# Loop_Schematic_r1_1_easyeda.net
KiCad netlist of a schematic drawn in EasyEDA
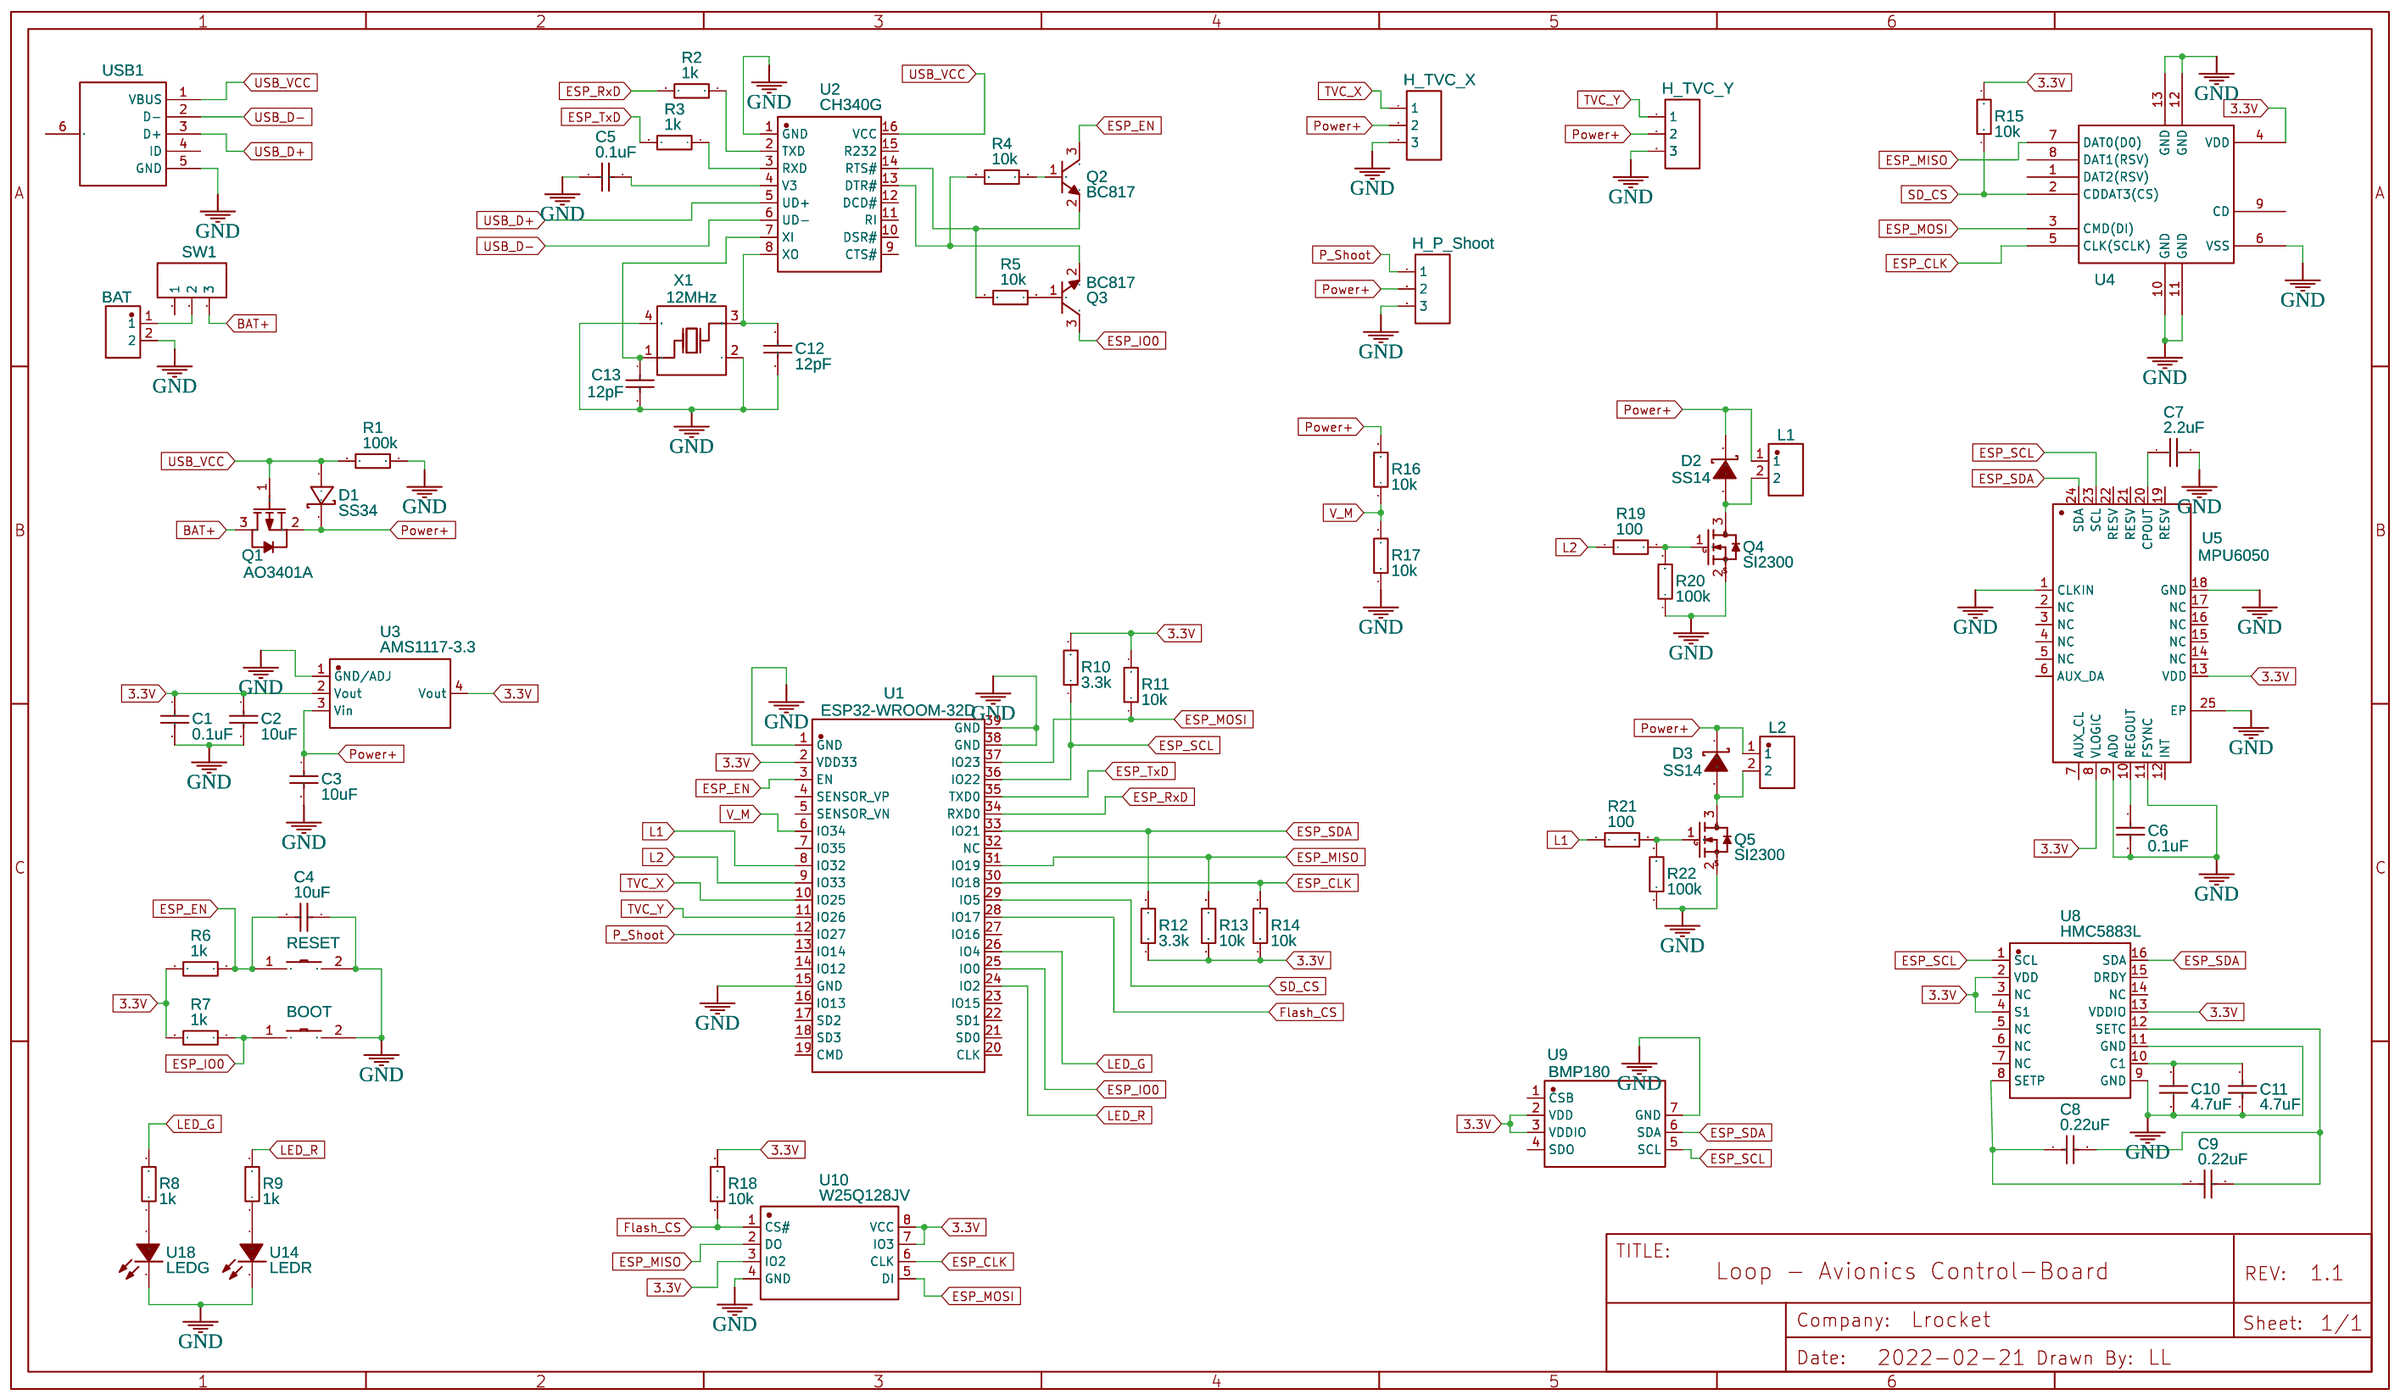
[diagram p0: schematic sheet]

(export (version "E")
  (design (tool "Eeschema 10.0.6"))
  (components
    (comp (ref "BAT")
      (value "XY308-2.54-2P")
      (fields (field (name "BOM_Supplier Part") "C557685"))
      (libsource (lib "") (part "XY308-2.54-2P"))
    )
    (comp (ref "BOOT")
      (value "TS-1101-C-W")
      (fields (field (name "BOM_Supplier Part") "C318938"))
      (libsource (lib "") (part "TS-1101-C-W_1"))
    )
    (comp (ref "C1")
      (value "0.1uF")
      (fields
        (field (name "BOM_Manufacturer Part") "CC0603KRX7R9BB103")
        (field (name "BOM_Supplier Part") "C100042")
      )
      (libsource (lib "") (part "CC0603KRX7R9BB103"))
    )
    (comp (ref "C2")
      (value "10uF")
      (fields
        (field (name "BOM_Manufacturer Part") "CC0603KRX7R9BB103")
        (field (name "BOM_Supplier Part") "C100042")
      )
      (libsource (lib "") (part "CC0603KRX7R9BB103"))
    )
    (comp (ref "C3")
      (value "10uF")
      (fields
        (field (name "BOM_Manufacturer Part") "CC0603KRX7R9BB103")
        (field (name "BOM_Supplier Part") "C100042")
      )
      (libsource (lib "") (part "CC0603KRX7R9BB103"))
    )
    (comp (ref "C4")
      (value "10uF")
      (fields
        (field (name "BOM_Manufacturer Part") "CC0603KRX7R9BB103")
        (field (name "BOM_Supplier Part") "C100042")
      )
      (libsource (lib "") (part "CC0603KRX7R9BB103_3"))
    )
    (comp (ref "C5")
      (value "0.1uF")
      (fields
        (field (name "BOM_Manufacturer Part") "CC0603KRX7R9BB103")
        (field (name "BOM_Supplier Part") "C100042")
      )
      (libsource (lib "") (part "CC0603KRX7R9BB103_3"))
    )
    (comp (ref "C6")
      (value "0.1uF")
      (fields
        (field (name "BOM_Manufacturer Part") "CC0603KRX7R9BB103")
        (field (name "BOM_Supplier Part") "C100042")
      )
      (libsource (lib "") (part "CC0603KRX7R9BB103_2"))
    )
    (comp (ref "C7")
      (value "2.2uF")
      (fields
        (field (name "BOM_Manufacturer Part") "CC0603KRX7R9BB103")
        (field (name "BOM_Supplier Part") "C100042")
      )
      (libsource (lib "") (part "CC0603KRX7R9BB103_1"))
    )
    (comp (ref "C8")
      (value "0.22uF")
      (fields
        (field (name "BOM_Manufacturer Part") "CC0603KRX7R9BB103")
        (field (name "BOM_Supplier Part") "C100042")
      )
      (libsource (lib "") (part "CC0603KRX7R9BB103_1"))
    )
    (comp (ref "C9")
      (value "0.22uF")
      (fields
        (field (name "BOM_Manufacturer Part") "DLC1.5P-C0805")
        (field (name "BOM_Supplier Part") "C9900002366")
      )
      (libsource (lib "") (part "DLC1.5P-C0805"))
    )
    (comp (ref "C10")
      (value "4.7uF")
      (fields
        (field (name "BOM_Manufacturer Part") "CC0603KRX7R9BB103")
        (field (name "BOM_Supplier Part") "C100042")
      )
      (libsource (lib "") (part "CC0603KRX7R9BB103"))
    )
    (comp (ref "C11")
      (value "4.7uF")
      (fields
        (field (name "BOM_Manufacturer Part") "DLC1.5P-C0805")
        (field (name "BOM_Supplier Part") "C9900002366")
      )
      (libsource (lib "") (part "DLC1.5P-C0805_1"))
    )
    (comp (ref "C12")
      (value "12pF")
      (fields
        (field (name "BOM_Manufacturer Part") "CC0603KRX7R9BB103")
        (field (name "BOM_Supplier Part") "C100042")
      )
      (libsource (lib "") (part "CC0603KRX7R9BB103"))
    )
    (comp (ref "C13")
      (value "12pF")
      (fields
        (field (name "BOM_Manufacturer Part") "CC0603KRX7R9BB103")
        (field (name "BOM_Supplier Part") "C100042")
      )
      (libsource (lib "") (part "CC0603KRX7R9BB103"))
    )
    (comp (ref "D1")
      (value "SS34")
      (fields (field (name "BOM_Supplier Part") "C8678"))
      (libsource (lib "") (part "SS34_C8678"))
    )
    (comp (ref "D2")
      (value "SS14")
      (fields (field (name "BOM_Supplier Part") "C2480"))
      (libsource (lib "") (part "SS14"))
    )
    (comp (ref "D3")
      (value "SS14")
      (fields (field (name "BOM_Supplier Part") "C2480"))
      (libsource (lib "") (part "SS14"))
    )
    (comp (ref "L1")
      (value "XY308-2.54-2P")
      (fields (field (name "BOM_Supplier Part") "C557685"))
      (libsource (lib "") (part "XY308-2.54-2P_1"))
    )
    (comp (ref "L2")
      (value "XY308-2.54-2P")
      (fields (field (name "BOM_Supplier Part") "C557685"))
      (libsource (lib "") (part "XY308-2.54-2P_1"))
    )
    (comp (ref "P_SHOOT")
      (value "H_P_Shoot")
      (fields
        (field (name "BOM_Manufacturer Part") "Header2.54mm 1*3P")
        (field (name "BOM_Supplier Part") "C49257")
      )
      (libsource (lib "") (part "Header-Male-2.54_1x3_2"))
    )
    (comp (ref "Q1")
      (value "AO3401A")
      (fields (field (name "BOM_Supplier Part") "C15127"))
      (libsource (lib "") (part "AO3401A"))
    )
    (comp (ref "Q2")
      (value "BC817")
      (fields (field (name "BOM_Manufacturer Part") "BC817-25") (field (name "BOM_Supplier Part") "C8588"))
      (libsource (lib "") (part "BC817-25"))
    )
    (comp (ref "Q3")
      (value "BC817")
      (fields (field (name "BOM_Manufacturer Part") "BC817-25") (field (name "BOM_Supplier Part") "C8588"))
      (libsource (lib "") (part "BC817-25_1"))
    )
    (comp (ref "Q4")
      (value "SI2300")
      (fields (field (name "BOM_Supplier Part") "C181085"))
      (libsource (lib "") (part "SI2300"))
    )
    (comp (ref "Q5")
      (value "SI2300")
      (fields (field (name "BOM_Supplier Part") "C181085"))
      (libsource (lib "") (part "SI2300"))
    )
    (comp (ref "R1")
      (value "100k")
      (fields
        (field (name "BOM_Manufacturer Part") "TR0603B10KP05250.1W")
        (field (name "BOM_Supplier Part") "C188363")
      )
      (libsource (lib "") (part "TR0603B10KP05250.1W_2"))
    )
    (comp (ref "R2")
      (value "1k")
      (fields
        (field (name "BOM_Manufacturer Part") "TR0603B10KP05250.1W")
        (field (name "BOM_Supplier Part") "C188363")
      )
      (libsource (lib "") (part "TR0603B10KP05250.1W_2"))
    )
    (comp (ref "R3")
      (value "1k")
      (fields
        (field (name "BOM_Manufacturer Part") "TR0603B10KP05250.1W")
        (field (name "BOM_Supplier Part") "C188363")
      )
      (libsource (lib "") (part "TR0603B10KP05250.1W_2"))
    )
    (comp (ref "R4")
      (value "10k")
      (fields
        (field (name "BOM_Manufacturer Part") "TR0603B10KP05250.1W")
        (field (name "BOM_Supplier Part") "C188363")
      )
      (libsource (lib "") (part "TR0603B10KP05250.1W_2"))
    )
    (comp (ref "R5")
      (value "10k")
      (fields
        (field (name "BOM_Manufacturer Part") "TR0603B10KP05250.1W")
        (field (name "BOM_Supplier Part") "C188363")
      )
      (libsource (lib "") (part "TR0603B10KP05250.1W_2"))
    )
    (comp (ref "R6")
      (value "1k")
      (fields
        (field (name "BOM_Manufacturer Part") "TR0603B10KP05250.1W")
        (field (name "BOM_Supplier Part") "C188363")
      )
      (libsource (lib "") (part "TR0603B10KP05250.1W_2"))
    )
    (comp (ref "R7")
      (value "1k")
      (fields
        (field (name "BOM_Manufacturer Part") "TR0603B10KP05250.1W")
        (field (name "BOM_Supplier Part") "C188363")
      )
      (libsource (lib "") (part "TR0603B10KP05250.1W_2"))
    )
    (comp (ref "R8")
      (value "1k")
      (fields
        (field (name "BOM_Manufacturer Part") "TR0603B10KP05250.1W")
        (field (name "BOM_Supplier Part") "C188363")
      )
      (libsource (lib "") (part "TR0603B10KP05250.1W"))
    )
    (comp (ref "R9")
      (value "1k")
      (fields
        (field (name "BOM_Manufacturer Part") "TR0603B10KP05250.1W")
        (field (name "BOM_Supplier Part") "C188363")
      )
      (libsource (lib "") (part "TR0603B10KP05250.1W"))
    )
    (comp (ref "R10")
      (value "3.3k")
      (fields
        (field (name "BOM_Manufacturer Part") "TR0603B10KP05250.1W")
        (field (name "BOM_Supplier Part") "C188363")
      )
      (libsource (lib "") (part "TR0603B10KP05250.1W"))
    )
    (comp (ref "R11")
      (value "10k")
      (fields
        (field (name "BOM_Manufacturer Part") "TR0603B10KP05250.1W")
        (field (name "BOM_Supplier Part") "C188363")
      )
      (libsource (lib "") (part "TR0603B10KP05250.1W"))
    )
    (comp (ref "R12")
      (value "3.3k")
      (fields
        (field (name "BOM_Manufacturer Part") "TR0603B10KP05250.1W")
        (field (name "BOM_Supplier Part") "C188363")
      )
      (libsource (lib "") (part "TR0603B10KP05250.1W"))
    )
    (comp (ref "R13")
      (value "10k")
      (fields
        (field (name "BOM_Manufacturer Part") "TR0603B10KP05250.1W")
        (field (name "BOM_Supplier Part") "C188363")
      )
      (libsource (lib "") (part "TR0603B10KP05250.1W"))
    )
    (comp (ref "R14")
      (value "10k")
      (fields
        (field (name "BOM_Manufacturer Part") "TR0603B10KP05250.1W")
        (field (name "BOM_Supplier Part") "C188363")
      )
      (libsource (lib "") (part "TR0603B10KP05250.1W"))
    )
    (comp (ref "R15")
      (value "10k")
      (fields
        (field (name "BOM_Manufacturer Part") "TR0603B10KP05250.1W")
        (field (name "BOM_Supplier Part") "C188363")
      )
      (libsource (lib "") (part "TR0603B10KP05250.1W"))
    )
    (comp (ref "R16")
      (value "10k")
      (fields
        (field (name "BOM_Manufacturer Part") "TR0603B10KP05250.1W")
        (field (name "BOM_Supplier Part") "C188363")
      )
      (libsource (lib "") (part "TR0603B10KP05250.1W"))
    )
    (comp (ref "R17")
      (value "10k")
      (fields
        (field (name "BOM_Manufacturer Part") "TR0603B10KP05250.1W")
        (field (name "BOM_Supplier Part") "C188363")
      )
      (libsource (lib "") (part "TR0603B10KP05250.1W"))
    )
    (comp (ref "R18")
      (value "10k")
      (fields
        (field (name "BOM_Manufacturer Part") "TR0603B10KP05250.1W")
        (field (name "BOM_Supplier Part") "C188363")
      )
      (libsource (lib "") (part "TR0603B10KP05250.1W"))
    )
    (comp (ref "R19")
      (value "100")
      (fields
        (field (name "BOM_Manufacturer Part") "TR0603B10KP05250.1W")
        (field (name "BOM_Supplier Part") "C188363")
      )
      (libsource (lib "") (part "TR0603B10KP05250.1W_1"))
    )
    (comp (ref "R20")
      (value "100k")
      (fields
        (field (name "BOM_Manufacturer Part") "TR0603B10KP05250.1W")
        (field (name "BOM_Supplier Part") "C188363")
      )
      (libsource (lib "") (part "TR0603B10KP05250.1W"))
    )
    (comp (ref "R21")
      (value "100")
      (fields
        (field (name "BOM_Manufacturer Part") "TR0603B10KP05250.1W")
        (field (name "BOM_Supplier Part") "C188363")
      )
      (libsource (lib "") (part "TR0603B10KP05250.1W_1"))
    )
    (comp (ref "R22")
      (value "100k")
      (fields
        (field (name "BOM_Manufacturer Part") "TR0603B10KP05250.1W")
        (field (name "BOM_Supplier Part") "C188363")
      )
      (libsource (lib "") (part "TR0603B10KP05250.1W"))
    )
    (comp (ref "RESET")
      (value "TS-1101-C-W")
      (fields (field (name "BOM_Supplier Part") "C318938"))
      (libsource (lib "") (part "TS-1101-C-W"))
    )
    (comp (ref "SW1")
      (value "SW1")
      (fields
        (field (name "BOM_Manufacturer Part") "Header2.54mm 1*3P")
        (field (name "BOM_Supplier Part") "C49257")
      )
      (libsource (lib "") (part "Header-Male-2.54_1x3_3"))
    )
    (comp (ref "TVC_X")
      (value "H_TVC_X")
      (fields
        (field (name "BOM_Manufacturer Part") "Header2.54mm 1*3P")
        (field (name "BOM_Supplier Part") "C49257")
      )
      (libsource (lib "") (part "Header-Male-2.54_1x3"))
    )
    (comp (ref "TVC_Y")
      (value "H_TVC_Y")
      (fields
        (field (name "BOM_Manufacturer Part") "Header2.54mm 1*3P")
        (field (name "BOM_Supplier Part") "C49257")
      )
      (libsource (lib "") (part "Header-Male-2.54_1x3_1"))
    )
    (comp (ref "U1")
      (value "ESP32-WROOM-32D")
      (fields (field (name "BOM_Supplier Part") "C473012"))
      (libsource (lib "") (part "ESP32-WROOM-32D"))
    )
    (comp (ref "U2")
      (value "CH340G")
      (fields (field (name "BOM_Supplier Part") "C14267"))
      (libsource (lib "") (part "CH340G"))
    )
    (comp (ref "U3")
      (value "AMS1117-3.3")
      (fields (field (name "BOM_Supplier Part") "C6186"))
      (libsource (lib "") (part "AMS1117-3.3"))
    )
    (comp (ref "U4")
      (value "TF-01A")
      (fields (field (name "BOM_Supplier Part") "C91145"))
      (libsource (lib "") (part "TF-01A"))
    )
    (comp (ref "U5")
      (value "MPU6050")
      (fields
        (field (name "BOM_Manufacturer Part") "MPU6050-YJLTY")
        (field (name "BOM_Supplier Part") "C2912107")
      )
      (libsource (lib "") (part "MPU6050-YJLTY"))
    )
    (comp (ref "U8")
      (value "HMC5883L")
      (fields (field (name "BOM_Supplier Part") "C2859540"))
      (libsource (lib "") (part "HMC5883L"))
    )
    (comp (ref "U9")
      (value "BMP180")
      (fields (field (name "BOM_Supplier Part") "C438474"))
      (libsource (lib "") (part "BMP180"))
    )
    (comp (ref "U10")
      (value "W25Q128JV")
      (fields
        (field (name "BOM_Manufacturer Part") "W25Q128JVSIQTR")
        (field (name "BOM_Supplier Part") "C97521")
      )
      (libsource (lib "") (part "W25Q128JVSIQTR"))
    )
    (comp (ref "U14")
      (value "LEDR")
      (fields (field (name "BOM_Manufacturer Part") "SZYY0603W") (field (name "BOM_Supplier Part") "C434422"))
      (libsource (lib "") (part "SZYY0603W"))
    )
    (comp (ref "U18")
      (value "LEDG")
      (fields (field (name "BOM_Manufacturer Part") "SZYY0603W") (field (name "BOM_Supplier Part") "C434422"))
      (libsource (lib "") (part "SZYY0603W"))
    )
    (comp (ref "USB1")
      (value "USB1")
      (fields
        (field (name "BOM_Manufacturer Part") "U254-051T-4BH83-S1S")
        (field (name "BOM_Supplier Part") "C319160")
      )
      (libsource (lib "") (part "U254-051T-4BH83-S1S"))
    )
    (comp (ref "X1")
      (value "12MHz")
      (fields
        (field (name "BOM_Manufacturer Part") "X322512MOB4SI")
        (field (name "BOM_Supplier Part") "C70565")
      )
      (libsource (lib "") (part "X322512MOB4SI"))
    )
  )
  (nets
    (net (code "1") (name "3.3V") (class "Default")
      (node (ref "C1") (pin "1") (pinfunction "1_1") (pintype "input"))
      (node (ref "C2") (pin "1") (pinfunction "1_1") (pintype "input"))
      (node (ref "R10") (pin "2") (pinfunction "2_2") (pintype "unspecified"))
      (node (ref "R11") (pin "2") (pinfunction "2_2") (pintype "unspecified"))
      (node (ref "R12") (pin "1") (pinfunction "1_1") (pintype "unspecified"))
      (node (ref "R13") (pin "1") (pinfunction "1_1") (pintype "unspecified"))
      (node (ref "R14") (pin "1") (pinfunction "1_1") (pintype "unspecified"))
      (node (ref "R15") (pin "2") (pinfunction "2_2") (pintype "unspecified"))
      (node (ref "R18") (pin "2") (pinfunction "2_2") (pintype "unspecified"))
      (node (ref "R6") (pin "2") (pinfunction "2_2") (pintype "unspecified"))
      (node (ref "R7") (pin "2") (pinfunction "2_2") (pintype "unspecified"))
      (node (ref "U1") (pin "2") (pinfunction "VDD33_2") (pintype "unspecified"))
      (node (ref "U10") (pin "3") (pinfunction "IO2_3") (pintype "unspecified"))
      (node (ref "U10") (pin "7") (pinfunction "IO3_7") (pintype "unspecified"))
      (node (ref "U10") (pin "8") (pinfunction "VCC_8") (pintype "unspecified"))
      (node (ref "U3") (pin "2") (pinfunction "Vout_2") (pintype "unspecified"))
      (node (ref "U3") (pin "4") (pinfunction "Vout_4") (pintype "unspecified"))
      (node (ref "U4") (pin "4") (pinfunction "VDD_4") (pintype "input"))
      (node (ref "U5") (pin "13") (pinfunction "VDD_13") (pintype "unspecified"))
      (node (ref "U5") (pin "8") (pinfunction "VLOGIC_8") (pintype "unspecified"))
      (node (ref "U8") (pin "13") (pinfunction "VDDIO_13") (pintype "unspecified"))
      (node (ref "U8") (pin "2") (pinfunction "VDD_2") (pintype "unspecified"))
      (node (ref "U8") (pin "4") (pinfunction "S1_4") (pintype "unspecified"))
      (node (ref "U9") (pin "2") (pinfunction "VDD_2") (pintype "unspecified"))
      (node (ref "U9") (pin "3") (pinfunction "VDDIO_3") (pintype "unspecified"))
    )
    (net (code "2") (name "BAT+") (class "Default")
      (node (ref "Q1") (pin "3") (pinfunction "D_3") (pintype "unspecified"))
      (node (ref "SW1") (pin "3") (pinfunction "3_3") (pintype "input"))
    )
    (net (code "3") (name "ESP_CLK") (class "Default")
      (node (ref "R14") (pin "2") (pinfunction "2_2") (pintype "unspecified"))
      (node (ref "U1") (pin "30") (pinfunction "IO18_30") (pintype "unspecified"))
      (node (ref "U10") (pin "6") (pinfunction "CLK_6") (pintype "unspecified"))
      (node (ref "U4") (pin "5") (pinfunction "CLK(SCLK)_5") (pintype "input"))
    )
    (net (code "4") (name "ESP_EN") (class "Default")
      (node (ref "C4") (pin "2") (pinfunction "2_2") (pintype "input"))
      (node (ref "Q2") (pin "3") (pinfunction "C_3") (pintype "unspecified"))
      (node (ref "R6") (pin "1") (pinfunction "1_1") (pintype "unspecified"))
      (node (ref "RESET") (pin "1") (pinfunction "1_1") (pintype "unspecified"))
      (node (ref "U1") (pin "3") (pinfunction "EN_3") (pintype "unspecified"))
    )
    (net (code "5") (name "ESP_IO0") (class "Default")
      (node (ref "BOOT") (pin "1") (pinfunction "1_1") (pintype "unspecified"))
      (node (ref "Q3") (pin "3") (pinfunction "C_3") (pintype "unspecified"))
      (node (ref "R7") (pin "1") (pinfunction "1_1") (pintype "unspecified"))
      (node (ref "U1") (pin "25") (pinfunction "IO0_25") (pintype "unspecified"))
    )
    (net (code "6") (name "ESP_MISO") (class "Default")
      (node (ref "R13") (pin "2") (pinfunction "2_2") (pintype "unspecified"))
      (node (ref "U1") (pin "31") (pinfunction "IO19_31") (pintype "unspecified"))
      (node (ref "U10") (pin "2") (pinfunction "DO_2") (pintype "unspecified"))
      (node (ref "U4") (pin "7") (pinfunction "DAT0(D0)_7") (pintype "bidirectional"))
    )
    (net (code "7") (name "ESP_MOSI") (class "Default")
      (node (ref "R11") (pin "1") (pinfunction "1_1") (pintype "unspecified"))
      (node (ref "U1") (pin "37") (pinfunction "IO23_37") (pintype "unspecified"))
      (node (ref "U10") (pin "5") (pinfunction "DI_5") (pintype "unspecified"))
      (node (ref "U4") (pin "3") (pinfunction "CMD(DI)_3") (pintype "input"))
    )
    (net (code "8") (name "ESP_RxD") (class "Default")
      (node (ref "R2") (pin "2") (pinfunction "2_2") (pintype "unspecified"))
      (node (ref "U1") (pin "34") (pinfunction "RXD0_34") (pintype "unspecified"))
    )
    (net (code "9") (name "ESP_SCL") (class "Default")
      (node (ref "R10") (pin "1") (pinfunction "1_1") (pintype "unspecified"))
      (node (ref "U1") (pin "36") (pinfunction "IO22_36") (pintype "unspecified"))
      (node (ref "U5") (pin "23") (pinfunction "SCL_23") (pintype "unspecified"))
      (node (ref "U8") (pin "1") (pinfunction "SCL_1") (pintype "unspecified"))
      (node (ref "U9") (pin "5") (pinfunction "SCL_5") (pintype "unspecified"))
    )
    (net (code "10") (name "ESP_SDA") (class "Default")
      (node (ref "R12") (pin "2") (pinfunction "2_2") (pintype "unspecified"))
      (node (ref "U1") (pin "33") (pinfunction "IO21_33") (pintype "unspecified"))
      (node (ref "U5") (pin "24") (pinfunction "SDA_24") (pintype "unspecified"))
      (node (ref "U8") (pin "16") (pinfunction "SDA_16") (pintype "unspecified"))
      (node (ref "U9") (pin "6") (pinfunction "SDA_6") (pintype "unspecified"))
    )
    (net (code "11") (name "ESP_TxD") (class "Default")
      (node (ref "R3") (pin "2") (pinfunction "2_2") (pintype "unspecified"))
      (node (ref "U1") (pin "35") (pinfunction "TXD0_35") (pintype "unspecified"))
    )
    (net (code "12") (name "Flash_CS") (class "Default")
      (node (ref "R18") (pin "1") (pinfunction "1_1") (pintype "unspecified"))
      (node (ref "U1") (pin "28") (pinfunction "IO17_28") (pintype "unspecified"))
      (node (ref "U10") (pin "1") (pinfunction "CS#_1") (pintype "unspecified"))
    )
    (net (code "13") (name "GND") (class "Default")
      (node (ref "BAT") (pin "2") (pinfunction "2_2") (pintype "unspecified"))
      (node (ref "BOOT") (pin "2") (pinfunction "2_2") (pintype "unspecified"))
      (node (ref "C1") (pin "2") (pinfunction "2_2") (pintype "input"))
      (node (ref "C10") (pin "2") (pinfunction "2_2") (pintype "input"))
      (node (ref "C11") (pin "2") (pinfunction "2_2") (pintype "input"))
      (node (ref "C12") (pin "2") (pinfunction "2_2") (pintype "input"))
      (node (ref "C13") (pin "2") (pinfunction "2_2") (pintype "input"))
      (node (ref "C2") (pin "2") (pinfunction "2_2") (pintype "input"))
      (node (ref "C3") (pin "2") (pinfunction "2_2") (pintype "input"))
      (node (ref "C4") (pin "1") (pinfunction "1_1") (pintype "input"))
      (node (ref "C5") (pin "2") (pinfunction "2_2") (pintype "input"))
      (node (ref "C6") (pin "1") (pinfunction "1_1") (pintype "input"))
      (node (ref "C7") (pin "2") (pinfunction "2_2") (pintype "input"))
      (node (ref "P_SHOOT") (pin "3") (pinfunction "3_3") (pintype "input"))
      (node (ref "Q4") (pin "2") (pinfunction "S_2") (pintype "unspecified"))
      (node (ref "Q5") (pin "2") (pinfunction "S_2") (pintype "unspecified"))
      (node (ref "R1") (pin "1") (pinfunction "1_1") (pintype "unspecified"))
      (node (ref "R17") (pin "1") (pinfunction "1_1") (pintype "unspecified"))
      (node (ref "R20") (pin "1") (pinfunction "1_1") (pintype "unspecified"))
      (node (ref "R22") (pin "1") (pinfunction "1_1") (pintype "unspecified"))
      (node (ref "RESET") (pin "2") (pinfunction "2_2") (pintype "unspecified"))
      (node (ref "TVC_X") (pin "3") (pinfunction "3_3") (pintype "input"))
      (node (ref "TVC_Y") (pin "3") (pinfunction "3_3") (pintype "input"))
      (node (ref "U1") (pin "1") (pinfunction "GND_1") (pintype "unspecified"))
      (node (ref "U1") (pin "15") (pinfunction "GND_15") (pintype "unspecified"))
      (node (ref "U1") (pin "38") (pinfunction "GND_38") (pintype "unspecified"))
      (node (ref "U1") (pin "39") (pinfunction "GND_39") (pintype "unspecified"))
      (node (ref "U10") (pin "4") (pinfunction "GND_4") (pintype "unspecified"))
      (node (ref "U14") (pin "2") (pinfunction "-_2") (pintype "unspecified"))
      (node (ref "U18") (pin "2") (pinfunction "-_2") (pintype "unspecified"))
      (node (ref "U2") (pin "1") (pinfunction "GND_1") (pintype "unspecified"))
      (node (ref "U3") (pin "1") (pinfunction "GND/ADJ_1") (pintype "unspecified"))
      (node (ref "U4") (pin "10") (pinfunction "GND_10") (pintype "input"))
      (node (ref "U4") (pin "11") (pinfunction "GND_11") (pintype "input"))
      (node (ref "U4") (pin "12") (pinfunction "GND_12") (pintype "input"))
      (node (ref "U4") (pin "13") (pinfunction "GND_13") (pintype "input"))
      (node (ref "U4") (pin "6") (pinfunction "VSS_6") (pintype "input"))
      (node (ref "U5") (pin "1") (pinfunction "CLKIN_1") (pintype "unspecified"))
      (node (ref "U5") (pin "11") (pinfunction "FSYNC_11") (pintype "unspecified"))
      (node (ref "U5") (pin "18") (pinfunction "GND_18") (pintype "unspecified"))
      (node (ref "U5") (pin "25") (pinfunction "EP_25") (pintype "unspecified"))
      (node (ref "U5") (pin "9") (pinfunction "AD0_9") (pintype "unspecified"))
      (node (ref "U8") (pin "11") (pinfunction "GND_11") (pintype "unspecified"))
      (node (ref "U8") (pin "9") (pinfunction "GND_9") (pintype "unspecified"))
      (node (ref "U9") (pin "7") (pinfunction "GND_7") (pintype "unspecified"))
      (node (ref "USB1") (pin "5") (pinfunction "GND_5") (pintype "input"))
      (node (ref "X1") (pin "2") (pinfunction "GND_2") (pintype "unspecified"))
      (node (ref "X1") (pin "4") (pinfunction "GND_4") (pintype "unspecified"))
    )
    (net (code "14") (name "L1") (class "Default")
      (node (ref "R21") (pin "1") (pinfunction "1_1") (pintype "unspecified"))
      (node (ref "U1") (pin "8") (pinfunction "IO32_8") (pintype "unspecified"))
    )
    (net (code "15") (name "L2") (class "Default")
      (node (ref "R19") (pin "1") (pinfunction "1_1") (pintype "unspecified"))
      (node (ref "U1") (pin "9") (pinfunction "IO33_9") (pintype "unspecified"))
    )
    (net (code "16") (name "LED_G") (class "Default")
      (node (ref "R8") (pin "2") (pinfunction "2_2") (pintype "unspecified"))
      (node (ref "U1") (pin "26") (pinfunction "IO4_26") (pintype "unspecified"))
    )
    (net (code "17") (name "LED_R") (class "Default")
      (node (ref "R9") (pin "2") (pinfunction "2_2") (pintype "unspecified"))
      (node (ref "U1") (pin "24") (pinfunction "IO2_24") (pintype "unspecified"))
    )
    (net (code "18") (name "Net-(BAT-Pad1)") (class "Default")
      (node (ref "BAT") (pin "1") (pinfunction "1_1") (pintype "unspecified"))
      (node (ref "SW1") (pin "2") (pinfunction "2_2") (pintype "input"))
    )
    (net (code "19") (name "Net-(D2-A)") (class "Default")
      (node (ref "D2") (pin "2") (pinfunction "A_2") (pintype "unspecified"))
      (node (ref "L1") (pin "2") (pinfunction "2_2") (pintype "unspecified"))
      (node (ref "Q4") (pin "3") (pinfunction "D_3") (pintype "unspecified"))
    )
    (net (code "20") (name "Net-(D3-A)") (class "Default")
      (node (ref "D3") (pin "2") (pinfunction "A_2") (pintype "unspecified"))
      (node (ref "L2") (pin "2") (pinfunction "2_2") (pintype "unspecified"))
      (node (ref "Q5") (pin "3") (pinfunction "D_3") (pintype "unspecified"))
    )
    (net (code "21") (name "Net-(Q2-B)") (class "Default")
      (node (ref "Q2") (pin "1") (pinfunction "B_1") (pintype "unspecified"))
      (node (ref "R4") (pin "1") (pinfunction "1_1") (pintype "unspecified"))
    )
    (net (code "22") (name "Net-(Q2-E)") (class "Default")
      (node (ref "Q2") (pin "2") (pinfunction "E_2") (pintype "unspecified"))
      (node (ref "R5") (pin "2") (pinfunction "2_2") (pintype "unspecified"))
      (node (ref "U2") (pin "14") (pinfunction "RTS#_14") (pintype "unspecified"))
    )
    (net (code "23") (name "Net-(Q3-B)") (class "Default")
      (node (ref "Q3") (pin "1") (pinfunction "B_1") (pintype "unspecified"))
      (node (ref "R5") (pin "1") (pinfunction "1_1") (pintype "unspecified"))
    )
    (net (code "24") (name "Net-(Q3-E)") (class "Default")
      (node (ref "Q3") (pin "2") (pinfunction "E_2") (pintype "unspecified"))
      (node (ref "R4") (pin "2") (pinfunction "2_2") (pintype "unspecified"))
      (node (ref "U2") (pin "13") (pinfunction "DTR#_13") (pintype "unspecified"))
    )
    (net (code "25") (name "Net-(Q4-G)") (class "Default")
      (node (ref "Q4") (pin "1") (pinfunction "G_1") (pintype "unspecified"))
      (node (ref "R19") (pin "2") (pinfunction "2_2") (pintype "unspecified"))
      (node (ref "R20") (pin "2") (pinfunction "2_2") (pintype "unspecified"))
    )
    (net (code "26") (name "Net-(Q5-G)") (class "Default")
      (node (ref "Q5") (pin "1") (pinfunction "G_1") (pintype "unspecified"))
      (node (ref "R21") (pin "2") (pinfunction "2_2") (pintype "unspecified"))
      (node (ref "R22") (pin "2") (pinfunction "2_2") (pintype "unspecified"))
    )
    (net (code "27") (name "Net-(U2-RXD)") (class "Default")
      (node (ref "R3") (pin "1") (pinfunction "1_1") (pintype "unspecified"))
      (node (ref "U2") (pin "3") (pinfunction "RXD_3") (pintype "unspecified"))
    )
    (net (code "28") (name "Net-(U2-TXD)") (class "Default")
      (node (ref "R2") (pin "1") (pinfunction "1_1") (pintype "unspecified"))
      (node (ref "U2") (pin "2") (pinfunction "TXD_2") (pintype "unspecified"))
    )
    (net (code "29") (name "Net-(U2-V3)") (class "Default")
      (node (ref "C5") (pin "1") (pinfunction "1_1") (pintype "input"))
      (node (ref "U2") (pin "4") (pinfunction "V3_4") (pintype "unspecified"))
    )
    (net (code "30") (name "Net-(U2-XI)") (class "Default")
      (node (ref "C13") (pin "1") (pinfunction "1_1") (pintype "input"))
      (node (ref "U2") (pin "7") (pinfunction "XI_7") (pintype "unspecified"))
      (node (ref "X1") (pin "1") (pinfunction "OSC1_1") (pintype "unspecified"))
    )
    (net (code "31") (name "Net-(U2-XO)") (class "Default")
      (node (ref "C12") (pin "1") (pinfunction "1_1") (pintype "input"))
      (node (ref "U2") (pin "8") (pinfunction "XO_8") (pintype "unspecified"))
      (node (ref "X1") (pin "3") (pinfunction "OSC2_3") (pintype "unspecified"))
    )
    (net (code "32") (name "Net-(U5-CPOUT)") (class "Default")
      (node (ref "C7") (pin "1") (pinfunction "1_1") (pintype "input"))
      (node (ref "U5") (pin "20") (pinfunction "CPOUT_20") (pintype "unspecified"))
    )
    (net (code "33") (name "Net-(U5-REGOUT)") (class "Default")
      (node (ref "C6") (pin "2") (pinfunction "2_2") (pintype "input"))
      (node (ref "U5") (pin "10") (pinfunction "REGOUT_10") (pintype "unspecified"))
    )
    (net (code "34") (name "Net-(U8-C1)") (class "Default")
      (node (ref "C10") (pin "1") (pinfunction "1_1") (pintype "input"))
      (node (ref "C11") (pin "1") (pinfunction "1_1") (pintype "input"))
      (node (ref "U8") (pin "10") (pinfunction "C1_10") (pintype "unspecified"))
    )
    (net (code "35") (name "Net-(U8-SETC)") (class "Default")
      (node (ref "C8") (pin "2") (pinfunction "2_2") (pintype "input"))
      (node (ref "C9") (pin "2") (pinfunction "2_2") (pintype "input"))
      (node (ref "U8") (pin "12") (pinfunction "SETC_12") (pintype "unspecified"))
    )
    (net (code "36") (name "Net-(U8-SETP)") (class "Default")
      (node (ref "C8") (pin "1") (pinfunction "1_1") (pintype "input"))
      (node (ref "C9") (pin "1") (pinfunction "1_1") (pintype "input"))
      (node (ref "U8") (pin "8") (pinfunction "SETP_8") (pintype "unspecified"))
    )
    (net (code "37") (name "Net-(U14-+)") (class "Default")
      (node (ref "R9") (pin "1") (pinfunction "1_1") (pintype "unspecified"))
      (node (ref "U14") (pin "1") (pinfunction "+_1") (pintype "unspecified"))
    )
    (net (code "38") (name "Net-(U18-+)") (class "Default")
      (node (ref "R8") (pin "1") (pinfunction "1_1") (pintype "unspecified"))
      (node (ref "U18") (pin "1") (pinfunction "+_1") (pintype "unspecified"))
    )
    (net (code "39") (name "P_Shoot") (class "Default")
      (node (ref "P_SHOOT") (pin "1") (pinfunction "1_1") (pintype "input"))
      (node (ref "U1") (pin "12") (pinfunction "IO27_12") (pintype "unspecified"))
    )
    (net (code "40") (name "Power+") (class "Default")
      (node (ref "C3") (pin "1") (pinfunction "1_1") (pintype "input"))
      (node (ref "D1") (pin "1") (pinfunction "K_1") (pintype "unspecified"))
      (node (ref "D2") (pin "1") (pinfunction "K_1") (pintype "unspecified"))
      (node (ref "D3") (pin "1") (pinfunction "K_1") (pintype "unspecified"))
      (node (ref "L1") (pin "1") (pinfunction "1_1") (pintype "unspecified"))
      (node (ref "L2") (pin "1") (pinfunction "1_1") (pintype "unspecified"))
      (node (ref "P_SHOOT") (pin "2") (pinfunction "2_2") (pintype "input"))
      (node (ref "Q1") (pin "2") (pinfunction "S_2") (pintype "unspecified"))
      (node (ref "R16") (pin "2") (pinfunction "2_2") (pintype "unspecified"))
      (node (ref "TVC_X") (pin "2") (pinfunction "2_2") (pintype "input"))
      (node (ref "TVC_Y") (pin "2") (pinfunction "2_2") (pintype "input"))
      (node (ref "U3") (pin "3") (pinfunction "Vin_3") (pintype "unspecified"))
    )
    (net (code "41") (name "SD_CS") (class "Default")
      (node (ref "R15") (pin "1") (pinfunction "1_1") (pintype "unspecified"))
      (node (ref "U1") (pin "29") (pinfunction "IO5_29") (pintype "unspecified"))
      (node (ref "U4") (pin "2") (pinfunction "CDDAT3(CS)_2") (pintype "bidirectional"))
    )
    (net (code "42") (name "TVC_X") (class "Default")
      (node (ref "TVC_X") (pin "1") (pinfunction "1_1") (pintype "input"))
      (node (ref "U1") (pin "10") (pinfunction "IO25_10") (pintype "unspecified"))
    )
    (net (code "43") (name "TVC_Y") (class "Default")
      (node (ref "TVC_Y") (pin "1") (pinfunction "1_1") (pintype "input"))
      (node (ref "U1") (pin "11") (pinfunction "IO26_11") (pintype "unspecified"))
    )
    (net (code "44") (name "USB_D+") (class "Default")
      (node (ref "U2") (pin "5") (pinfunction "UD+_5") (pintype "unspecified"))
      (node (ref "USB1") (pin "3") (pinfunction "D+_3") (pintype "input"))
    )
    (net (code "45") (name "USB_D-") (class "Default")
      (node (ref "U2") (pin "6") (pinfunction "UD-_6") (pintype "unspecified"))
      (node (ref "USB1") (pin "2") (pinfunction "D-_2") (pintype "input"))
    )
    (net (code "46") (name "USB_VCC") (class "Default")
      (node (ref "D1") (pin "2") (pinfunction "A_2") (pintype "unspecified"))
      (node (ref "Q1") (pin "1") (pinfunction "G_1") (pintype "unspecified"))
      (node (ref "R1") (pin "2") (pinfunction "2_2") (pintype "unspecified"))
      (node (ref "U2") (pin "16") (pinfunction "VCC_16") (pintype "unspecified"))
      (node (ref "USB1") (pin "1") (pinfunction "VBUS_1") (pintype "input"))
    )
    (net (code "47") (name "V_M") (class "Default")
      (node (ref "R16") (pin "1") (pinfunction "1_1") (pintype "unspecified"))
      (node (ref "R17") (pin "2") (pinfunction "2_2") (pintype "unspecified"))
      (node (ref "U1") (pin "6") (pinfunction "IO34_6") (pintype "unspecified"))
    )
    (net (code "48") (name "unconnected-(SW1-Pad1)") (class "Default")
      (node (ref "SW1") (pin "1") (pinfunction "1_1") (pintype "input"))
    )
    (net (code "49") (name "unconnected-(U1-CLK-Pad20)") (class "Default")
      (node (ref "U1") (pin "20") (pinfunction "CLK_20") (pintype "unspecified"))
    )
    (net (code "50") (name "unconnected-(U1-CMD-Pad19)") (class "Default")
      (node (ref "U1") (pin "19") (pinfunction "CMD_19") (pintype "unspecified"))
    )
    (net (code "51") (name "unconnected-(U1-IO12-Pad14)") (class "Default")
      (node (ref "U1") (pin "14") (pinfunction "IO12_14") (pintype "unspecified"))
    )
    (net (code "52") (name "unconnected-(U1-IO13-Pad16)") (class "Default")
      (node (ref "U1") (pin "16") (pinfunction "IO13_16") (pintype "unspecified"))
    )
    (net (code "53") (name "unconnected-(U1-IO14-Pad13)") (class "Default")
      (node (ref "U1") (pin "13") (pinfunction "IO14_13") (pintype "unspecified"))
    )
    (net (code "54") (name "unconnected-(U1-IO15-Pad23)") (class "Default")
      (node (ref "U1") (pin "23") (pinfunction "IO15_23") (pintype "unspecified"))
    )
    (net (code "55") (name "unconnected-(U1-IO16-Pad27)") (class "Default")
      (node (ref "U1") (pin "27") (pinfunction "IO16_27") (pintype "unspecified"))
    )
    (net (code "56") (name "unconnected-(U1-IO35-Pad7)") (class "Default")
      (node (ref "U1") (pin "7") (pinfunction "IO35_7") (pintype "unspecified"))
    )
    (net (code "57") (name "unconnected-(U1-NC-Pad32)") (class "Default")
      (node (ref "U1") (pin "32") (pinfunction "NC_32") (pintype "unspecified"))
    )
    (net (code "58") (name "unconnected-(U1-SD0-Pad21)") (class "Default")
      (node (ref "U1") (pin "21") (pinfunction "SD0_21") (pintype "unspecified"))
    )
    (net (code "59") (name "unconnected-(U1-SD1-Pad22)") (class "Default")
      (node (ref "U1") (pin "22") (pinfunction "SD1_22") (pintype "unspecified"))
    )
    (net (code "60") (name "unconnected-(U1-SD2-Pad17)") (class "Default")
      (node (ref "U1") (pin "17") (pinfunction "SD2_17") (pintype "unspecified"))
    )
    (net (code "61") (name "unconnected-(U1-SD3-Pad18)") (class "Default")
      (node (ref "U1") (pin "18") (pinfunction "SD3_18") (pintype "unspecified"))
    )
    (net (code "62") (name "unconnected-(U1-SENSOR_VN-Pad5)") (class "Default")
      (node (ref "U1") (pin "5") (pinfunction "SENSOR_VN_5") (pintype "unspecified"))
    )
    (net (code "63") (name "unconnected-(U1-SENSOR_VP-Pad4)") (class "Default")
      (node (ref "U1") (pin "4") (pinfunction "SENSOR_VP_4") (pintype "unspecified"))
    )
    (net (code "64") (name "unconnected-(U2-CTS#-Pad9)") (class "Default")
      (node (ref "U2") (pin "9") (pinfunction "CTS#_9") (pintype "unspecified"))
    )
    (net (code "65") (name "unconnected-(U2-DCD#-Pad12)") (class "Default")
      (node (ref "U2") (pin "12") (pinfunction "DCD#_12") (pintype "unspecified"))
    )
    (net (code "66") (name "unconnected-(U2-DSR#-Pad10)") (class "Default")
      (node (ref "U2") (pin "10") (pinfunction "DSR#_10") (pintype "unspecified"))
    )
    (net (code "67") (name "unconnected-(U2-R232-Pad15)") (class "Default")
      (node (ref "U2") (pin "15") (pinfunction "R232_15") (pintype "unspecified"))
    )
    (net (code "68") (name "unconnected-(U2-RI-Pad11)") (class "Default")
      (node (ref "U2") (pin "11") (pinfunction "RI_11") (pintype "unspecified"))
    )
    (net (code "69") (name "unconnected-(U4-CD-Pad9)") (class "Default")
      (node (ref "U4") (pin "9") (pinfunction "CD_9") (pintype "input"))
    )
    (net (code "70") (name "unconnected-(U4-DAT1(RSV)-Pad8)") (class "Default")
      (node (ref "U4") (pin "8") (pinfunction "DAT1(RSV)_8") (pintype "bidirectional"))
    )
    (net (code "71") (name "unconnected-(U4-DAT2(RSV)-Pad1)") (class "Default")
      (node (ref "U4") (pin "1") (pinfunction "DAT2(RSV)_1") (pintype "bidirectional"))
    )
    (net (code "72") (name "unconnected-(U5-AUX_CL-Pad7)") (class "Default")
      (node (ref "U5") (pin "7") (pinfunction "AUX_CL_7") (pintype "unspecified"))
    )
    (net (code "73") (name "unconnected-(U5-AUX_DA-Pad6)") (class "Default")
      (node (ref "U5") (pin "6") (pinfunction "AUX_DA_6") (pintype "unspecified"))
    )
    (net (code "74") (name "unconnected-(U5-INT-Pad12)") (class "Default")
      (node (ref "U5") (pin "12") (pinfunction "INT_12") (pintype "unspecified"))
    )
    (net (code "75") (name "unconnected-(U5-NC-Pad2)") (class "Default")
      (node (ref "U5") (pin "2") (pinfunction "NC_2") (pintype "unspecified"))
    )
    (net (code "76") (name "unconnected-(U5-NC-Pad3)") (class "Default")
      (node (ref "U5") (pin "3") (pinfunction "NC_3") (pintype "unspecified"))
    )
    (net (code "77") (name "unconnected-(U5-NC-Pad4)") (class "Default")
      (node (ref "U5") (pin "4") (pinfunction "NC_4") (pintype "unspecified"))
    )
    (net (code "78") (name "unconnected-(U5-NC-Pad5)") (class "Default")
      (node (ref "U5") (pin "5") (pinfunction "NC_5") (pintype "unspecified"))
    )
    (net (code "79") (name "unconnected-(U5-NC-Pad14)") (class "Default")
      (node (ref "U5") (pin "14") (pinfunction "NC_14") (pintype "unspecified"))
    )
    (net (code "80") (name "unconnected-(U5-NC-Pad15)") (class "Default")
      (node (ref "U5") (pin "15") (pinfunction "NC_15") (pintype "unspecified"))
    )
    (net (code "81") (name "unconnected-(U5-NC-Pad16)") (class "Default")
      (node (ref "U5") (pin "16") (pinfunction "NC_16") (pintype "unspecified"))
    )
    (net (code "82") (name "unconnected-(U5-NC-Pad17)") (class "Default")
      (node (ref "U5") (pin "17") (pinfunction "NC_17") (pintype "unspecified"))
    )
    (net (code "83") (name "unconnected-(U5-RESV-Pad19)") (class "Default")
      (node (ref "U5") (pin "19") (pinfunction "RESV_19") (pintype "unspecified"))
    )
    (net (code "84") (name "unconnected-(U5-RESV-Pad21)") (class "Default")
      (node (ref "U5") (pin "21") (pinfunction "RESV_21") (pintype "unspecified"))
    )
    (net (code "85") (name "unconnected-(U5-RESV-Pad22)") (class "Default")
      (node (ref "U5") (pin "22") (pinfunction "RESV_22") (pintype "unspecified"))
    )
    (net (code "86") (name "unconnected-(U8-DRDY-Pad15)") (class "Default")
      (node (ref "U8") (pin "15") (pinfunction "DRDY_15") (pintype "unspecified"))
    )
    (net (code "87") (name "unconnected-(U8-NC-Pad3)") (class "Default")
      (node (ref "U8") (pin "3") (pinfunction "NC_3") (pintype "unspecified"))
    )
    (net (code "88") (name "unconnected-(U8-NC-Pad5)") (class "Default")
      (node (ref "U8") (pin "5") (pinfunction "NC_5") (pintype "unspecified"))
    )
    (net (code "89") (name "unconnected-(U8-NC-Pad6)") (class "Default")
      (node (ref "U8") (pin "6") (pinfunction "NC_6") (pintype "unspecified"))
    )
    (net (code "90") (name "unconnected-(U8-NC-Pad7)") (class "Default")
      (node (ref "U8") (pin "7") (pinfunction "NC_7") (pintype "unspecified"))
    )
    (net (code "91") (name "unconnected-(U8-NC-Pad14)") (class "Default")
      (node (ref "U8") (pin "14") (pinfunction "NC_14") (pintype "unspecified"))
    )
    (net (code "92") (name "unconnected-(U9-CSB-Pad1)") (class "Default")
      (node (ref "U9") (pin "1") (pinfunction "CSB_1") (pintype "unspecified"))
    )
    (net (code "93") (name "unconnected-(U9-SDO-Pad4)") (class "Default")
      (node (ref "U9") (pin "4") (pinfunction "SDO_4") (pintype "unspecified"))
    )
    (net (code "94") (name "unconnected-(USB1-EH-Pad6)") (class "Default")
      (node (ref "USB1") (pin "6") (pinfunction "EH_6") (pintype "input"))
    )
    (net (code "95") (name "unconnected-(USB1-ID-Pad4)") (class "Default")
      (node (ref "USB1") (pin "4") (pinfunction "ID_4") (pintype "input"))
    )
  )
)
